# 13thISE_ver9.net
KiCad netlist of a schematic drawn in EAGLE
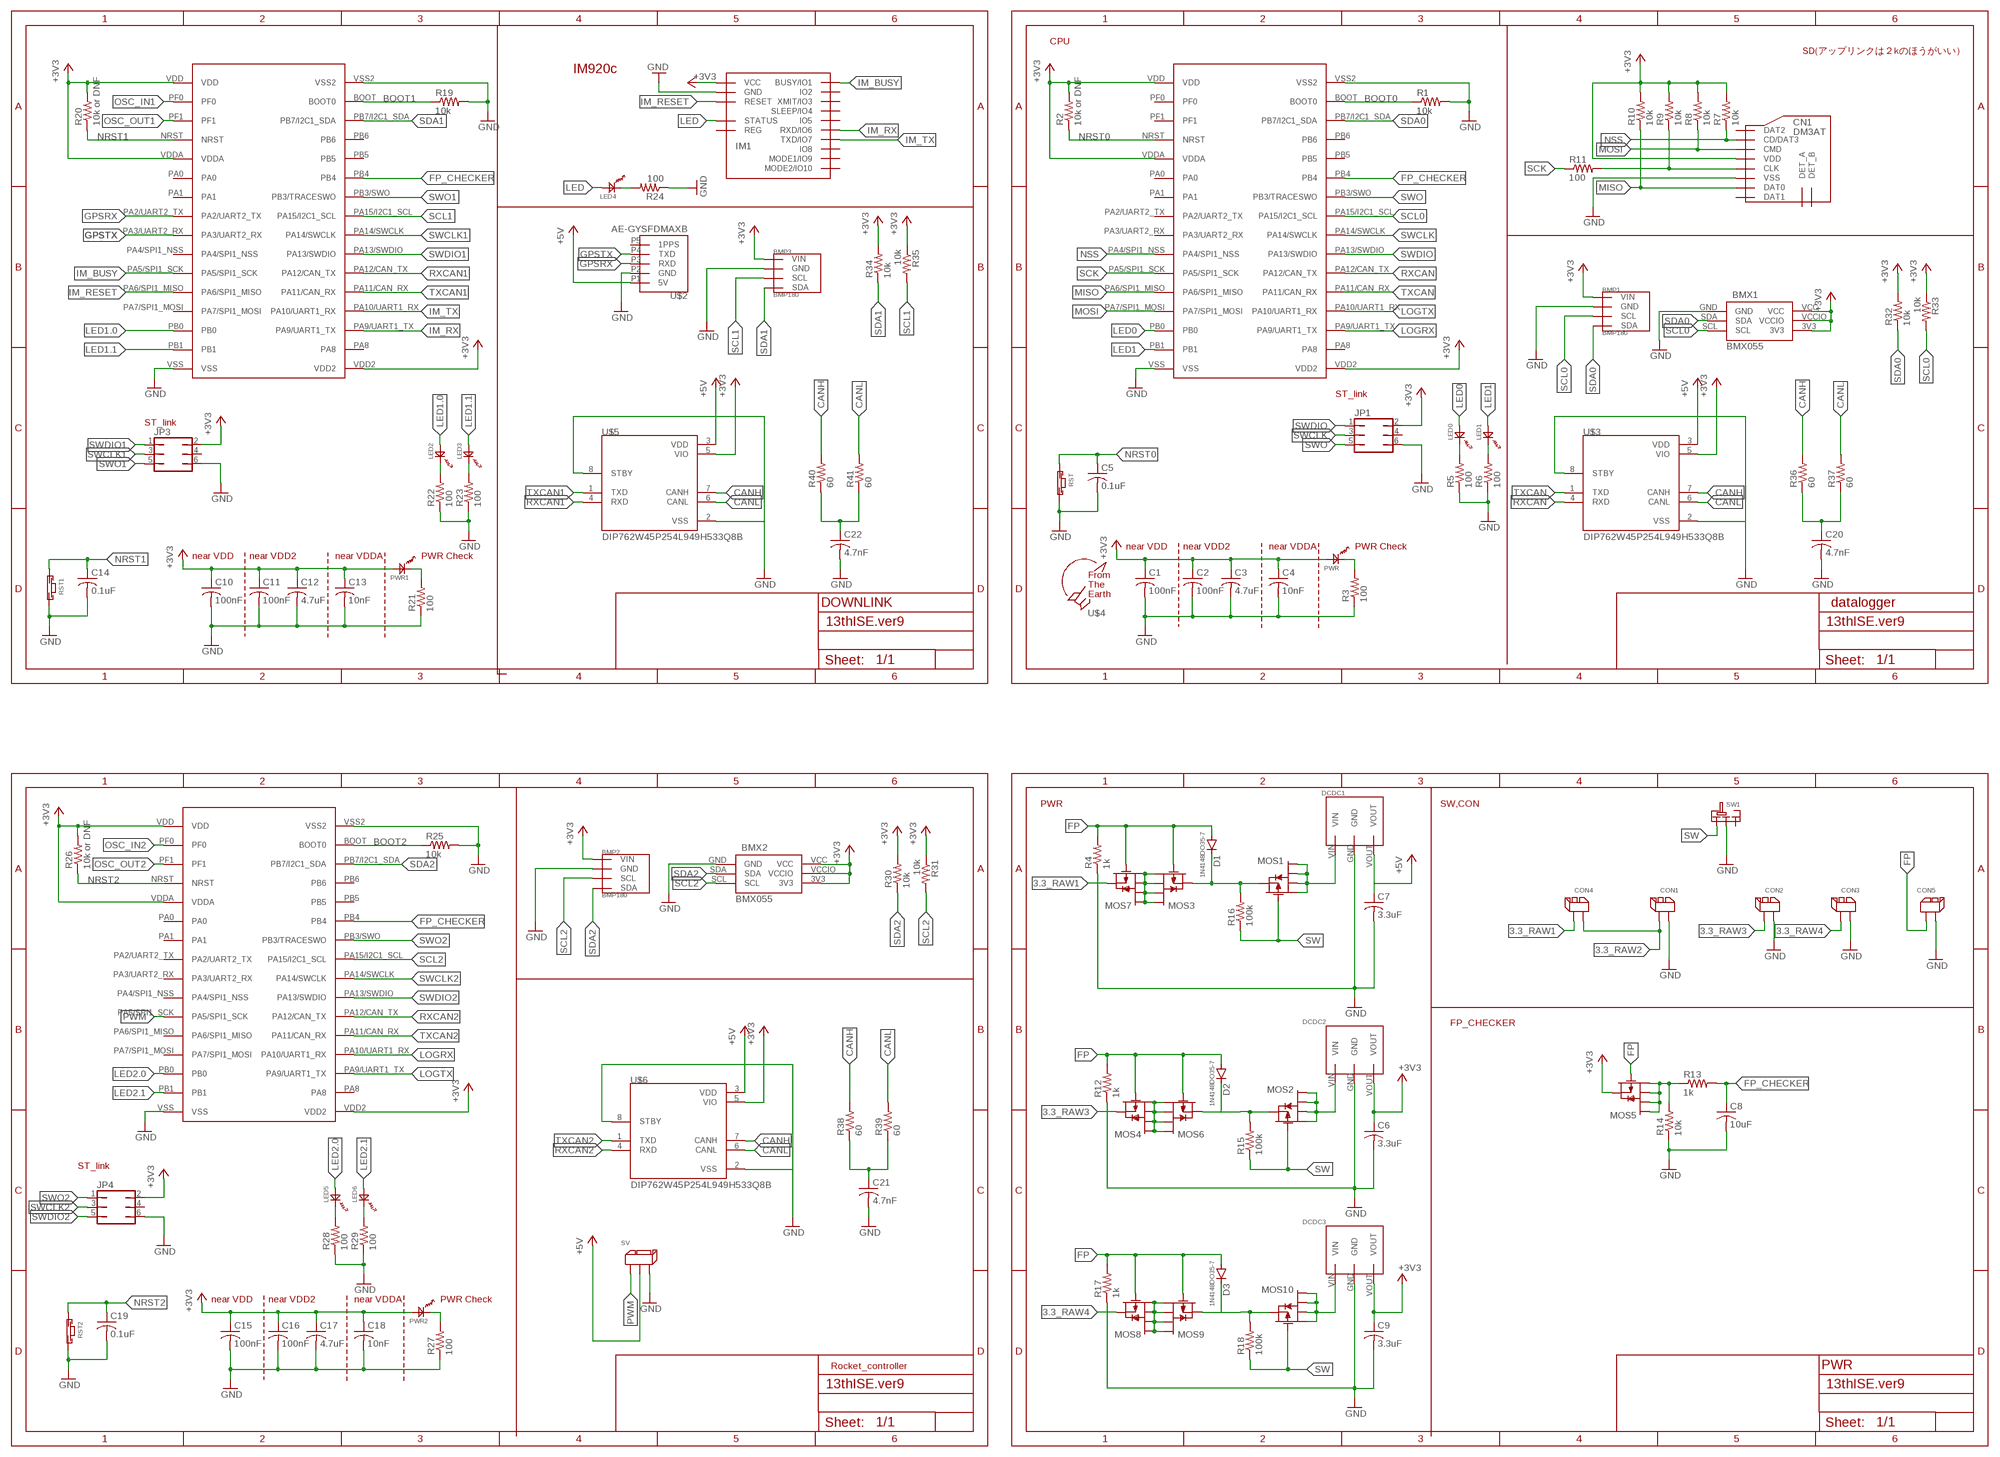
[diagram p0: schematic, sheet 1]

(export (version "E")
  (design (tool "Eeschema 10.0.6"))
  (components
    (comp (ref "BMP1")
      (value "BMP180")
      (footprint "eagle-import:GY-68")
      (libsource (lib "eagle-import") (part "BMP180"))
    )
    (comp (ref "BMP2")
      (value "BMP180")
      (footprint "eagle-import:GY-68")
      (libsource (lib "eagle-import") (part "BMP180"))
    )
    (comp (ref "BMP3")
      (value "BMP180")
      (footprint "eagle-import:GY-68")
      (libsource (lib "eagle-import") (part "BMP180"))
    )
    (comp (ref "BMX1")
      (value "BMX055")
      (footprint "eagle-import:BMX055")
      (libsource (lib "eagle-import") (part "BMX055"))
    )
    (comp (ref "BMX2")
      (value "BMX055")
      (footprint "eagle-import:BMX055")
      (libsource (lib "eagle-import") (part "BMX055"))
    )
    (comp (ref "C1")
      (value "100nF")
      (footprint "eagle-import:C1608")
      (libsource (lib "eagle-import") (part "C-USC1608"))
    )
    (comp (ref "C2")
      (value "100nF")
      (footprint "eagle-import:C1608")
      (libsource (lib "eagle-import") (part "C-USC1608"))
    )
    (comp (ref "C3")
      (value "4.7uF")
      (footprint "eagle-import:C1608")
      (libsource (lib "eagle-import") (part "C-USC1608"))
    )
    (comp (ref "C4")
      (value "10nF")
      (footprint "eagle-import:C1608")
      (libsource (lib "eagle-import") (part "C-USC1608"))
    )
    (comp (ref "C5")
      (value "0.1uF")
      (footprint "eagle-import:C1608")
      (libsource (lib "eagle-import") (part "C-USC1608"))
    )
    (comp (ref "C6")
      (value "3.3uF")
      (footprint "eagle-import:C0603")
      (libsource (lib "eagle-import") (part "C-USC0603"))
    )
    (comp (ref "C7")
      (value "3.3uF")
      (footprint "eagle-import:C0603")
      (libsource (lib "eagle-import") (part "C-USC0603"))
    )
    (comp (ref "C8")
      (value "10uF")
      (footprint "eagle-import:C0603")
      (libsource (lib "eagle-import") (part "C-USC0603"))
    )
    (comp (ref "C9")
      (value "3.3uF")
      (footprint "eagle-import:C0603")
      (libsource (lib "eagle-import") (part "C-USC0603"))
    )
    (comp (ref "C10")
      (value "100nF")
      (footprint "eagle-import:C1608")
      (libsource (lib "eagle-import") (part "C-USC1608"))
    )
    (comp (ref "C11")
      (value "100nF")
      (footprint "eagle-import:C1608")
      (libsource (lib "eagle-import") (part "C-USC1608"))
    )
    (comp (ref "C12")
      (value "4.7uF")
      (footprint "eagle-import:C1608")
      (libsource (lib "eagle-import") (part "C-USC1608"))
    )
    (comp (ref "C13")
      (value "10nF")
      (footprint "eagle-import:C1608")
      (libsource (lib "eagle-import") (part "C-USC1608"))
    )
    (comp (ref "C14")
      (value "0.1uF")
      (footprint "eagle-import:C1608")
      (libsource (lib "eagle-import") (part "C-USC1608"))
    )
    (comp (ref "C15")
      (value "100nF")
      (footprint "eagle-import:C1608")
      (libsource (lib "eagle-import") (part "C-USC1608"))
    )
    (comp (ref "C16")
      (value "100nF")
      (footprint "eagle-import:C1608")
      (libsource (lib "eagle-import") (part "C-USC1608"))
    )
    (comp (ref "C17")
      (value "4.7uF")
      (footprint "eagle-import:C1608")
      (libsource (lib "eagle-import") (part "C-USC1608"))
    )
    (comp (ref "C18")
      (value "10nF")
      (footprint "eagle-import:C1608")
      (libsource (lib "eagle-import") (part "C-USC1608"))
    )
    (comp (ref "C19")
      (value "0.1uF")
      (footprint "eagle-import:C1608")
      (libsource (lib "eagle-import") (part "C-USC1608"))
    )
    (comp (ref "C20")
      (value "4.7nF")
      (footprint "eagle-import:C0603")
      (libsource (lib "eagle-import") (part "C-USC0603"))
    )
    (comp (ref "C21")
      (value "4.7nF")
      (footprint "eagle-import:C0603")
      (libsource (lib "eagle-import") (part "C-USC0603"))
    )
    (comp (ref "C22")
      (value "4.7nF")
      (footprint "eagle-import:C0603")
      (libsource (lib "eagle-import") (part "C-USC0603"))
    )
    (comp (ref "CN1")
      (value "DM3AT")
      (footprint "eagle-import:DM3AT")
      (libsource (lib "eagle-import") (part "DM3AT"))
    )
    (comp (ref "CON1")
      (value "2PIN")
      (footprint "eagle-import:2PIN")
      (libsource (lib "eagle-import") (part "2PIN"))
    )
    (comp (ref "CON2")
      (value "2PIN")
      (footprint "eagle-import:2PIN")
      (libsource (lib "eagle-import") (part "2PIN"))
    )
    (comp (ref "CON3")
      (value "2PIN")
      (footprint "eagle-import:2PIN")
      (libsource (lib "eagle-import") (part "2PIN"))
    )
    (comp (ref "CON4")
      (value "2PIN")
      (footprint "eagle-import:2PIN")
      (libsource (lib "eagle-import") (part "2PIN"))
    )
    (comp (ref "CON5")
      (value "2PIN")
      (footprint "eagle-import:2PIN")
      (libsource (lib "eagle-import") (part "2PIN"))
    )
    (comp (ref "D1")
      (value "1N4148DO35-7")
      (footprint "eagle-import:DO35-7")
      (libsource (lib "eagle-import") (part "1N4148DO35-7"))
    )
    (comp (ref "D2")
      (value "1N4148DO35-7")
      (footprint "eagle-import:DO35-7")
      (libsource (lib "eagle-import") (part "1N4148DO35-7"))
    )
    (comp (ref "D3")
      (value "1N4148DO35-7")
      (footprint "eagle-import:DO35-7")
      (libsource (lib "eagle-import") (part "1N4148DO35-7"))
    )
    (comp (ref "DCDC1")
      (value "5V1A_M78AR05-1")
      (footprint "eagle-import:5V1A_M78AR05-1")
      (libsource (lib "eagle-import") (part "5V1A_M78AR05-1"))
    )
    (comp (ref "DCDC2")
      (value "3.3V1A_M78AR033-1")
      (footprint "eagle-import:3.3V1A_M78AR033-1")
      (libsource (lib "eagle-import") (part "3.3V1A_M78AR033-1"))
    )
    (comp (ref "DCDC3")
      (value "3.3V1A_M78AR033-1")
      (footprint "eagle-import:3.3V1A_M78AR033-1")
      (libsource (lib "eagle-import") (part "3.3V1A_M78AR033-1"))
    )
    (comp (ref "IM1")
      (value "IM920_IM920C")
      (footprint "eagle-import:IM920_IM920C")
      (libsource (lib "eagle-import") (part "IM920_IM920C"))
    )
    (comp (ref "JP1")
      (value "JP3Q")
      (footprint "eagle-import:JP3Q")
      (libsource (lib "eagle-import") (part "JP3Q"))
    )
    (comp (ref "JP3")
      (value "JP3Q")
      (footprint "eagle-import:JP3Q")
      (libsource (lib "eagle-import") (part "JP3Q"))
    )
    (comp (ref "JP4")
      (value "JP3Q")
      (footprint "eagle-import:JP3Q")
      (libsource (lib "eagle-import") (part "JP3Q"))
    )
    (comp (ref "LED0")
      (value "OSXX1608C1A")
      (footprint "eagle-import:OSXX1608C1A")
      (libsource (lib "eagle-import") (part "OSXX1608C1A"))
    )
    (comp (ref "LED1")
      (value "OSXX1608C1A")
      (footprint "eagle-import:OSXX1608C1A")
      (libsource (lib "eagle-import") (part "OSXX1608C1A"))
    )
    (comp (ref "LED2")
      (value "OSXX1608C1A")
      (footprint "eagle-import:OSXX1608C1A")
      (libsource (lib "eagle-import") (part "OSXX1608C1A"))
    )
    (comp (ref "LED3")
      (value "OSXX1608C1A")
      (footprint "eagle-import:OSXX1608C1A")
      (libsource (lib "eagle-import") (part "OSXX1608C1A"))
    )
    (comp (ref "LED4")
      (value "OSXX1608C1A")
      (footprint "eagle-import:OSXX1608C1A")
      (libsource (lib "eagle-import") (part "OSXX1608C1A"))
    )
    (comp (ref "LED5")
      (value "OSXX1608C1A")
      (footprint "eagle-import:OSXX1608C1A")
      (libsource (lib "eagle-import") (part "OSXX1608C1A"))
    )
    (comp (ref "LED6")
      (value "OSXX1608C1A")
      (footprint "eagle-import:OSXX1608C1A")
      (libsource (lib "eagle-import") (part "OSXX1608C1A"))
    )
    (comp (ref "MOS1")
      (value "PCH_SSM6J808R")
      (footprint "eagle-import:SSM6J808R")
      (libsource (lib "eagle-import") (part "PCH_SSM6J808R"))
    )
    (comp (ref "MOS2")
      (value "PCH_SSM6J808R")
      (footprint "eagle-import:SSM6J808R")
      (libsource (lib "eagle-import") (part "PCH_SSM6J808R"))
    )
    (comp (ref "MOS3")
      (value "PCH_SSM6J808R")
      (footprint "eagle-import:SSM6J808R")
      (libsource (lib "eagle-import") (part "PCH_SSM6J808R"))
    )
    (comp (ref "MOS4")
      (value "PCH_SSM6J808R")
      (footprint "eagle-import:SSM6J808R")
      (libsource (lib "eagle-import") (part "PCH_SSM6J808R"))
    )
    (comp (ref "MOS5")
      (value "PCH_SSM6J808R")
      (footprint "eagle-import:SSM6J808R")
      (libsource (lib "eagle-import") (part "PCH_SSM6J808R"))
    )
    (comp (ref "MOS6")
      (value "PCH_SSM6J808R")
      (footprint "eagle-import:SSM6J808R")
      (libsource (lib "eagle-import") (part "PCH_SSM6J808R"))
    )
    (comp (ref "MOS7")
      (value "PCH_SSM6J808R")
      (footprint "eagle-import:SSM6J808R")
      (libsource (lib "eagle-import") (part "PCH_SSM6J808R"))
    )
    (comp (ref "MOS8")
      (value "PCH_SSM6J808R")
      (footprint "eagle-import:SSM6J808R")
      (libsource (lib "eagle-import") (part "PCH_SSM6J808R"))
    )
    (comp (ref "MOS9")
      (value "PCH_SSM6J808R")
      (footprint "eagle-import:SSM6J808R")
      (libsource (lib "eagle-import") (part "PCH_SSM6J808R"))
    )
    (comp (ref "MOS10")
      (value "PCH_SSM6J808R")
      (footprint "eagle-import:SSM6J808R")
      (libsource (lib "eagle-import") (part "PCH_SSM6J808R"))
    )
    (comp (ref "PWR")
      (value "OSXX1608C1A")
      (footprint "eagle-import:OSXX1608C1A")
      (libsource (lib "eagle-import") (part "OSXX1608C1A"))
    )
    (comp (ref "PWR1")
      (value "OSXX1608C1A")
      (footprint "eagle-import:OSXX1608C1A")
      (libsource (lib "eagle-import") (part "OSXX1608C1A"))
    )
    (comp (ref "PWR2")
      (value "OSXX1608C1A")
      (footprint "eagle-import:OSXX1608C1A")
      (libsource (lib "eagle-import") (part "OSXX1608C1A"))
    )
    (comp (ref "R1")
      (value "10k")
      (footprint "eagle-import:R0603")
      (libsource (lib "eagle-import") (part "R-US_R0603"))
    )
    (comp (ref "R2")
      (value "10k or DNF")
      (footprint "eagle-import:R0603")
      (libsource (lib "eagle-import") (part "R-US_R0603"))
    )
    (comp (ref "R3")
      (value "100")
      (footprint "eagle-import:R0603")
      (libsource (lib "eagle-import") (part "R-US_R0603"))
    )
    (comp (ref "R4")
      (value "1k")
      (footprint "eagle-import:R0603")
      (libsource (lib "eagle-import") (part "R-US_R0603"))
    )
    (comp (ref "R5")
      (value "100")
      (footprint "eagle-import:R0603")
      (libsource (lib "eagle-import") (part "R-US_R0603"))
    )
    (comp (ref "R6")
      (value "100")
      (footprint "eagle-import:R0603")
      (libsource (lib "eagle-import") (part "R-US_R0603"))
    )
    (comp (ref "R7")
      (value "10k")
      (footprint "eagle-import:R0603")
      (libsource (lib "eagle-import") (part "R-US_R0603"))
    )
    (comp (ref "R8")
      (value "10k")
      (footprint "eagle-import:R0603")
      (libsource (lib "eagle-import") (part "R-US_R0603"))
    )
    (comp (ref "R9")
      (value "10k")
      (footprint "eagle-import:R0603")
      (libsource (lib "eagle-import") (part "R-US_R0603"))
    )
    (comp (ref "R10")
      (value "10k")
      (footprint "eagle-import:R0603")
      (libsource (lib "eagle-import") (part "R-US_R0603"))
    )
    (comp (ref "R11")
      (value "100")
      (footprint "eagle-import:R0603")
      (libsource (lib "eagle-import") (part "R-US_R0603"))
    )
    (comp (ref "R12")
      (value "1k")
      (footprint "eagle-import:R0603")
      (libsource (lib "eagle-import") (part "R-US_R0603"))
    )
    (comp (ref "R13")
      (value "1k")
      (footprint "eagle-import:R0603")
      (libsource (lib "eagle-import") (part "R-US_R0603"))
    )
    (comp (ref "R14")
      (value "10k")
      (footprint "eagle-import:R0603")
      (libsource (lib "eagle-import") (part "R-US_R0603"))
    )
    (comp (ref "R15")
      (value "100k")
      (footprint "eagle-import:R0603")
      (libsource (lib "eagle-import") (part "R-US_R0603"))
    )
    (comp (ref "R16")
      (value "100k")
      (footprint "eagle-import:R0603")
      (libsource (lib "eagle-import") (part "R-US_R0603"))
    )
    (comp (ref "R17")
      (value "1k")
      (footprint "eagle-import:R0603")
      (libsource (lib "eagle-import") (part "R-US_R0603"))
    )
    (comp (ref "R18")
      (value "100k")
      (footprint "eagle-import:R0603")
      (libsource (lib "eagle-import") (part "R-US_R0603"))
    )
    (comp (ref "R19")
      (value "10k")
      (footprint "eagle-import:R0603")
      (libsource (lib "eagle-import") (part "R-US_R0603"))
    )
    (comp (ref "R20")
      (value "10k or DNF")
      (footprint "eagle-import:R0603")
      (libsource (lib "eagle-import") (part "R-US_R0603"))
    )
    (comp (ref "R21")
      (value "100")
      (footprint "eagle-import:R0603")
      (libsource (lib "eagle-import") (part "R-US_R0603"))
    )
    (comp (ref "R22")
      (value "100")
      (footprint "eagle-import:R0603")
      (libsource (lib "eagle-import") (part "R-US_R0603"))
    )
    (comp (ref "R23")
      (value "100")
      (footprint "eagle-import:R0603")
      (libsource (lib "eagle-import") (part "R-US_R0603"))
    )
    (comp (ref "R24")
      (value "100")
      (footprint "eagle-import:R0603")
      (libsource (lib "eagle-import") (part "R-US_R0603"))
    )
    (comp (ref "R25")
      (value "10k")
      (footprint "eagle-import:R0603")
      (libsource (lib "eagle-import") (part "R-US_R0603"))
    )
    (comp (ref "R26")
      (value "10k or DNF")
      (footprint "eagle-import:R0603")
      (libsource (lib "eagle-import") (part "R-US_R0603"))
    )
    (comp (ref "R27")
      (value "100")
      (footprint "eagle-import:R0603")
      (libsource (lib "eagle-import") (part "R-US_R0603"))
    )
    (comp (ref "R28")
      (value "100")
      (footprint "eagle-import:R0603")
      (libsource (lib "eagle-import") (part "R-US_R0603"))
    )
    (comp (ref "R29")
      (value "100")
      (footprint "eagle-import:R0603")
      (libsource (lib "eagle-import") (part "R-US_R0603"))
    )
    (comp (ref "R30")
      (value "10k")
      (footprint "eagle-import:R0603")
      (libsource (lib "eagle-import") (part "R-US_R0603"))
    )
    (comp (ref "R31")
      (value "10k")
      (footprint "eagle-import:R0603")
      (libsource (lib "eagle-import") (part "R-US_R0603"))
    )
    (comp (ref "R32")
      (value "10k")
      (footprint "eagle-import:R0603")
      (libsource (lib "eagle-import") (part "R-US_R0603"))
    )
    (comp (ref "R33")
      (value "10k")
      (footprint "eagle-import:R0603")
      (libsource (lib "eagle-import") (part "R-US_R0603"))
    )
    (comp (ref "R34")
      (value "10k")
      (footprint "eagle-import:R0603")
      (libsource (lib "eagle-import") (part "R-US_R0603"))
    )
    (comp (ref "R35")
      (value "10k")
      (footprint "eagle-import:R0603")
      (libsource (lib "eagle-import") (part "R-US_R0603"))
    )
    (comp (ref "R36")
      (value "60")
      (footprint "eagle-import:R0603")
      (libsource (lib "eagle-import") (part "R-US_R0603"))
    )
    (comp (ref "R37")
      (value "60")
      (footprint "eagle-import:R0603")
      (libsource (lib "eagle-import") (part "R-US_R0603"))
    )
    (comp (ref "R38")
      (value "60")
      (footprint "eagle-import:R0603")
      (libsource (lib "eagle-import") (part "R-US_R0603"))
    )
    (comp (ref "R39")
      (value "60")
      (footprint "eagle-import:R0603")
      (libsource (lib "eagle-import") (part "R-US_R0603"))
    )
    (comp (ref "R40")
      (value "60")
      (footprint "eagle-import:R0603")
      (libsource (lib "eagle-import") (part "R-US_R0603"))
    )
    (comp (ref "R41")
      (value "60")
      (footprint "eagle-import:R0603")
      (libsource (lib "eagle-import") (part "R-US_R0603"))
    )
    (comp (ref "RST")
      (value "TVAF06-A020B-R")
      (footprint "eagle-import:TVAF06-A020B-R")
      (libsource (lib "eagle-import") (part "TVAF06-A020B-R"))
    )
    (comp (ref "RST1")
      (value "TVAF06-A020B-R")
      (footprint "eagle-import:TVAF06-A020B-R")
      (libsource (lib "eagle-import") (part "TVAF06-A020B-R"))
    )
    (comp (ref "RST2")
      (value "TVAF06-A020B-R")
      (footprint "eagle-import:TVAF06-A020B-R")
      (libsource (lib "eagle-import") (part "TVAF06-A020B-R"))
    )
    (comp (ref "STM0")
      (value "STM32F303K8")
      (footprint "eagle-import:STM32F303K8")
      (libsource (lib "eagle-import") (part "STM32F303K8"))
    )
    (comp (ref "STM1")
      (value "STM32F303K8")
      (footprint "eagle-import:STM32F303K8")
      (libsource (lib "eagle-import") (part "STM32F303K8"))
    )
    (comp (ref "SV")
      (value "3PIN")
      (footprint "eagle-import:3PIN")
      (libsource (lib "eagle-import") (part "3PIN"))
    )
    (comp (ref "SW1")
      (value "SRIDE_SWITCH")
      (footprint "eagle-import:SRIDE_SWITCH")
      (libsource (lib "eagle-import") (part "SRIDE_SWITCH"))
    )
    (comp (ref "U$1")
      (value "STM32F303K8")
      (footprint "eagle-import:STM32F303K8")
      (libsource (lib "eagle-import") (part "STM32F303K8"))
    )
    (comp (ref "U$2")
      (value "AE-GYSFDMAXB")
      (footprint "eagle-import:AE-GYSFDMAXB")
      (libsource (lib "eagle-import") (part "AE-GYSFDMAXB"))
    )
    (comp (ref "U$3")
      (value "DIP762W45P254L949H533Q8B")
      (footprint "eagle-import:DIP762W45P254L949H533Q8B")
      (libsource (lib "eagle-import") (part "DIP762W45P254L949H533Q8B"))
    )
    (comp (ref "U$4")
      (value "F.T.E.LOGO")
      (footprint "eagle-import:LOGO")
      (libsource (lib "eagle-import") (part "F.T.E.LOGO"))
    )
    (comp (ref "U$5")
      (value "DIP762W45P254L949H533Q8B")
      (footprint "eagle-import:DIP762W45P254L949H533Q8B")
      (libsource (lib "eagle-import") (part "DIP762W45P254L949H533Q8B"))
    )
    (comp (ref "U$6")
      (value "DIP762W45P254L949H533Q8B")
      (footprint "eagle-import:DIP762W45P254L949H533Q8B")
      (libsource (lib "eagle-import") (part "DIP762W45P254L949H533Q8B"))
    )
  )
  (nets
    (net (code "1") (name "+3V3") (class "Default")
      (node (ref "BMP1") (pin "P1") (pinfunction "VIN_P1") (pintype "bidirectional"))
      (node (ref "BMP2") (pin "P1") (pinfunction "VIN_P1") (pintype "bidirectional"))
      (node (ref "BMP3") (pin "P1") (pinfunction "VIN_P1") (pintype "bidirectional"))
      (node (ref "BMX1") (pin "3V3") (pinfunction "3V3_3V3") (pintype "power_in"))
      (node (ref "BMX1") (pin "VCC") (pinfunction "VCC_VCC") (pintype "power_in"))
      (node (ref "BMX1") (pin "VCCIO") (pinfunction "VCCIO_VCCIO") (pintype "power_in"))
      (node (ref "BMX2") (pin "3V3") (pinfunction "3V3_3V3") (pintype "power_in"))
      (node (ref "BMX2") (pin "VCC") (pinfunction "VCC_VCC") (pintype "power_in"))
      (node (ref "BMX2") (pin "VCCIO") (pinfunction "VCCIO_VCCIO") (pintype "power_in"))
      (node (ref "C1") (pin "1") (pinfunction "1_1") (pintype "passive"))
      (node (ref "C10") (pin "1") (pinfunction "1_1") (pintype "passive"))
      (node (ref "C11") (pin "1") (pinfunction "1_1") (pintype "passive"))
      (node (ref "C12") (pin "1") (pinfunction "1_1") (pintype "passive"))
      (node (ref "C13") (pin "1") (pinfunction "1_1") (pintype "passive"))
      (node (ref "C15") (pin "1") (pinfunction "1_1") (pintype "passive"))
      (node (ref "C16") (pin "1") (pinfunction "1_1") (pintype "passive"))
      (node (ref "C17") (pin "1") (pinfunction "1_1") (pintype "passive"))
      (node (ref "C18") (pin "1") (pinfunction "1_1") (pintype "passive"))
      (node (ref "C2") (pin "1") (pinfunction "1_1") (pintype "passive"))
      (node (ref "C3") (pin "1") (pinfunction "1_1") (pintype "passive"))
      (node (ref "C4") (pin "1") (pinfunction "1_1") (pintype "passive"))
      (node (ref "C6") (pin "1") (pinfunction "1_1") (pintype "passive"))
      (node (ref "C9") (pin "1") (pinfunction "1_1") (pintype "passive"))
      (node (ref "CN1") (pin "VDD") (pinfunction "VDD_VDD") (pintype "bidirectional"))
      (node (ref "DCDC2") (pin "VOUT") (pinfunction "VOUT_VOUT") (pintype "bidirectional"))
      (node (ref "DCDC3") (pin "VOUT") (pinfunction "VOUT_VOUT") (pintype "bidirectional"))
      (node (ref "IM1") (pin "$P17") (pinfunction "VCC_$P17") (pintype "bidirectional"))
      (node (ref "JP1") (pin "2") (pinfunction "2_2") (pintype "passive"))
      (node (ref "JP3") (pin "2") (pinfunction "2_2") (pintype "passive"))
      (node (ref "JP4") (pin "2") (pinfunction "2_2") (pintype "passive"))
      (node (ref "MOS5") (pin "4") (pinfunction "4_4") (pintype "bidirectional"))
      (node (ref "PWR") (pin "AN") (pinfunction "AN_AN") (pintype "bidirectional"))
      (node (ref "PWR1") (pin "AN") (pinfunction "AN_AN") (pintype "bidirectional"))
      (node (ref "PWR2") (pin "AN") (pinfunction "AN_AN") (pintype "bidirectional"))
      (node (ref "R10") (pin "2") (pinfunction "2_2") (pintype "passive"))
      (node (ref "R2") (pin "2") (pinfunction "2_2") (pintype "passive"))
      (node (ref "R20") (pin "2") (pinfunction "2_2") (pintype "passive"))
      (node (ref "R26") (pin "2") (pinfunction "2_2") (pintype "passive"))
      (node (ref "R30") (pin "2") (pinfunction "2_2") (pintype "passive"))
      (node (ref "R31") (pin "1") (pinfunction "1_1") (pintype "passive"))
      (node (ref "R32") (pin "2") (pinfunction "2_2") (pintype "passive"))
      (node (ref "R33") (pin "1") (pinfunction "1_1") (pintype "passive"))
      (node (ref "R34") (pin "2") (pinfunction "2_2") (pintype "passive"))
      (node (ref "R35") (pin "1") (pinfunction "1_1") (pintype "passive"))
      (node (ref "R7") (pin "2") (pinfunction "2_2") (pintype "passive"))
      (node (ref "R8") (pin "2") (pinfunction "2_2") (pintype "passive"))
      (node (ref "R9") (pin "2") (pinfunction "2_2") (pintype "passive"))
      (node (ref "STM0") (pin "VDD") (pinfunction "VDD_VDD") (pintype "power_in"))
      (node (ref "STM0") (pin "VDD2") (pinfunction "VDD2_VDD2") (pintype "power_in"))
      (node (ref "STM0") (pin "VDDA") (pinfunction "VDDA_VDDA") (pintype "power_in"))
      (node (ref "STM1") (pin "VDD") (pinfunction "VDD_VDD") (pintype "power_in"))
      (node (ref "STM1") (pin "VDD2") (pinfunction "VDD2_VDD2") (pintype "power_in"))
      (node (ref "STM1") (pin "VDDA") (pinfunction "VDDA_VDDA") (pintype "power_in"))
      (node (ref "U$1") (pin "VDD") (pinfunction "VDD_VDD") (pintype "power_in"))
      (node (ref "U$1") (pin "VDD2") (pinfunction "VDD2_VDD2") (pintype "power_in"))
      (node (ref "U$1") (pin "VDDA") (pinfunction "VDDA_VDDA") (pintype "power_in"))
      (node (ref "U$3") (pin "5") (pinfunction "VIO_5") (pintype "power_in"))
      (node (ref "U$5") (pin "5") (pinfunction "VIO_5") (pintype "power_in"))
      (node (ref "U$6") (pin "5") (pinfunction "VIO_5") (pintype "power_in"))
    )
    (net (code "2") (name "+5V") (class "Default")
      (node (ref "C7") (pin "1") (pinfunction "1_1") (pintype "passive"))
      (node (ref "DCDC1") (pin "VOUT") (pinfunction "VOUT_VOUT") (pintype "bidirectional"))
      (node (ref "SV") (pin "P$2") (pinfunction "P$2_P$2") (pintype "bidirectional"))
      (node (ref "U$2") (pin "P1") (pinfunction "5V_P1") (pintype "bidirectional"))
      (node (ref "U$3") (pin "3") (pinfunction "VDD_3") (pintype "power_in"))
      (node (ref "U$5") (pin "3") (pinfunction "VDD_3") (pintype "power_in"))
      (node (ref "U$6") (pin "3") (pinfunction "VDD_3") (pintype "power_in"))
    )
    (net (code "3") (name "/BOOT0") (class "Default")
      (node (ref "R1") (pin "1") (pinfunction "1_1") (pintype "passive"))
      (node (ref "STM0") (pin "BOOT") (pinfunction "BOOT0_BOOT") (pintype "bidirectional"))
    )
    (net (code "4") (name "/BOOT1") (class "Default")
      (node (ref "R19") (pin "1") (pinfunction "1_1") (pintype "passive"))
      (node (ref "STM1") (pin "BOOT") (pinfunction "BOOT0_BOOT") (pintype "bidirectional"))
    )
    (net (code "5") (name "/BOOT2") (class "Default")
      (node (ref "R25") (pin "1") (pinfunction "1_1") (pintype "passive"))
      (node (ref "U$1") (pin "BOOT") (pinfunction "BOOT0_BOOT") (pintype "bidirectional"))
    )
    (net (code "6") (name "3.3_RAW1") (class "Default")
      (node (ref "CON4") (pin "P$2") (pinfunction "P$2_P$2") (pintype "bidirectional"))
      (node (ref "MOS7") (pin "4") (pinfunction "4_4") (pintype "bidirectional"))
    )
    (net (code "7") (name "3.3_RAW2") (class "Default")
      (node (ref "CON1") (pin "P$2") (pinfunction "P$2_P$2") (pintype "bidirectional"))
      (node (ref "CON4") (pin "P$1") (pinfunction "P$1_P$1") (pintype "bidirectional"))
    )
    (net (code "8") (name "3.3_RAW3") (class "Default")
      (node (ref "CON2") (pin "P$2") (pinfunction "P$2_P$2") (pintype "bidirectional"))
      (node (ref "MOS4") (pin "4") (pinfunction "4_4") (pintype "bidirectional"))
    )
    (net (code "9") (name "3.3_RAW4") (class "Default")
      (node (ref "CON3") (pin "P$2") (pinfunction "P$2_P$2") (pintype "bidirectional"))
      (node (ref "MOS8") (pin "4") (pinfunction "4_4") (pintype "bidirectional"))
    )
    (net (code "10") (name "CANH") (class "Default")
      (node (ref "R36") (pin "2") (pinfunction "2_2") (pintype "passive"))
      (node (ref "R38") (pin "2") (pinfunction "2_2") (pintype "passive"))
      (node (ref "R40") (pin "2") (pinfunction "2_2") (pintype "passive"))
      (node (ref "U$3") (pin "7") (pinfunction "CANH_7") (pintype "bidirectional"))
      (node (ref "U$5") (pin "7") (pinfunction "CANH_7") (pintype "bidirectional"))
      (node (ref "U$6") (pin "7") (pinfunction "CANH_7") (pintype "bidirectional"))
    )
    (net (code "11") (name "CANL") (class "Default")
      (node (ref "R37") (pin "2") (pinfunction "2_2") (pintype "passive"))
      (node (ref "R39") (pin "2") (pinfunction "2_2") (pintype "passive"))
      (node (ref "R41") (pin "2") (pinfunction "2_2") (pintype "passive"))
      (node (ref "U$3") (pin "6") (pinfunction "CANL_6") (pintype "bidirectional"))
      (node (ref "U$5") (pin "6") (pinfunction "CANL_6") (pintype "bidirectional"))
      (node (ref "U$6") (pin "6") (pinfunction "CANL_6") (pintype "bidirectional"))
    )
    (net (code "12") (name "FP") (class "Default")
      (node (ref "CON5") (pin "P$1") (pinfunction "P$1_P$1") (pintype "bidirectional"))
      (node (ref "D1") (pin "A") (pinfunction "A_A") (pintype "passive"))
      (node (ref "D2") (pin "A") (pinfunction "A_A") (pintype "passive"))
      (node (ref "D3") (pin "A") (pinfunction "A_A") (pintype "passive"))
      (node (ref "MOS3") (pin "3") (pinfunction "3_3") (pintype "bidirectional"))
      (node (ref "MOS4") (pin "3") (pinfunction "3_3") (pintype "bidirectional"))
      (node (ref "MOS5") (pin "3") (pinfunction "3_3") (pintype "bidirectional"))
      (node (ref "MOS6") (pin "3") (pinfunction "3_3") (pintype "bidirectional"))
      (node (ref "MOS7") (pin "3") (pinfunction "3_3") (pintype "bidirectional"))
      (node (ref "MOS8") (pin "3") (pinfunction "3_3") (pintype "bidirectional"))
      (node (ref "MOS9") (pin "3") (pinfunction "3_3") (pintype "bidirectional"))
      (node (ref "R12") (pin "2") (pinfunction "2_2") (pintype "passive"))
      (node (ref "R17") (pin "2") (pinfunction "2_2") (pintype "passive"))
      (node (ref "R4") (pin "2") (pinfunction "2_2") (pintype "passive"))
    )
    (net (code "13") (name "FP_CHECKER") (class "Default")
      (node (ref "C8") (pin "1") (pinfunction "1_1") (pintype "passive"))
      (node (ref "R13") (pin "2") (pinfunction "2_2") (pintype "passive"))
      (node (ref "STM0") (pin "PB4") (pinfunction "PB4_PB4") (pintype "bidirectional"))
      (node (ref "STM1") (pin "PB4") (pinfunction "PB4_PB4") (pintype "bidirectional"))
      (node (ref "U$1") (pin "PB4") (pinfunction "PB4_PB4") (pintype "bidirectional"))
    )
    (net (code "14") (name "GND") (class "Default")
      (node (ref "BMP1") (pin "P2") (pinfunction "GND_P2") (pintype "bidirectional"))
      (node (ref "BMP2") (pin "P2") (pinfunction "GND_P2") (pintype "bidirectional"))
      (node (ref "BMP3") (pin "P2") (pinfunction "GND_P2") (pintype "bidirectional"))
      (node (ref "BMX1") (pin "GND") (pinfunction "GND_GND") (pintype "power_in"))
      (node (ref "BMX2") (pin "GND") (pinfunction "GND_GND") (pintype "power_in"))
      (node (ref "C1") (pin "2") (pinfunction "2_2") (pintype "passive"))
      (node (ref "C10") (pin "2") (pinfunction "2_2") (pintype "passive"))
      (node (ref "C11") (pin "2") (pinfunction "2_2") (pintype "passive"))
      (node (ref "C12") (pin "2") (pinfunction "2_2") (pintype "passive"))
      (node (ref "C13") (pin "2") (pinfunction "2_2") (pintype "passive"))
      (node (ref "C14") (pin "2") (pinfunction "2_2") (pintype "passive"))
      (node (ref "C15") (pin "2") (pinfunction "2_2") (pintype "passive"))
      (node (ref "C16") (pin "2") (pinfunction "2_2") (pintype "passive"))
      (node (ref "C17") (pin "2") (pinfunction "2_2") (pintype "passive"))
      (node (ref "C18") (pin "2") (pinfunction "2_2") (pintype "passive"))
      (node (ref "C19") (pin "2") (pinfunction "2_2") (pintype "passive"))
      (node (ref "C2") (pin "2") (pinfunction "2_2") (pintype "passive"))
      (node (ref "C20") (pin "2") (pinfunction "2_2") (pintype "passive"))
      (node (ref "C21") (pin "2") (pinfunction "2_2") (pintype "passive"))
      (node (ref "C22") (pin "2") (pinfunction "2_2") (pintype "passive"))
      (node (ref "C3") (pin "2") (pinfunction "2_2") (pintype "passive"))
      (node (ref "C4") (pin "2") (pinfunction "2_2") (pintype "passive"))
      (node (ref "C5") (pin "2") (pinfunction "2_2") (pintype "passive"))
      (node (ref "C6") (pin "2") (pinfunction "2_2") (pintype "passive"))
      (node (ref "C7") (pin "2") (pinfunction "2_2") (pintype "passive"))
      (node (ref "C8") (pin "2") (pinfunction "2_2") (pintype "passive"))
      (node (ref "C9") (pin "2") (pinfunction "2_2") (pintype "passive"))
      (node (ref "CN1") (pin "VSS") (pinfunction "VSS_VSS") (pintype "bidirectional"))
      (node (ref "CON1") (pin "P$1") (pinfunction "P$1_P$1") (pintype "bidirectional"))
      (node (ref "CON2") (pin "P$1") (pinfunction "P$1_P$1") (pintype "bidirectional"))
      (node (ref "CON3") (pin "P$1") (pinfunction "P$1_P$1") (pintype "bidirectional"))
      (node (ref "CON5") (pin "P$2") (pinfunction "P$2_P$2") (pintype "bidirectional"))
      (node (ref "DCDC1") (pin "GND") (pinfunction "GND_GND") (pintype "bidirectional"))
      (node (ref "DCDC2") (pin "GND") (pinfunction "GND_GND") (pintype "bidirectional"))
      (node (ref "DCDC3") (pin "GND") (pinfunction "GND_GND") (pintype "bidirectional"))
      (node (ref "IM1") (pin "$P18") (pinfunction "GND_$P18") (pintype "bidirectional"))
      (node (ref "JP1") (pin "6") (pinfunction "6_6") (pintype "passive"))
      (node (ref "JP3") (pin "6") (pinfunction "6_6") (pintype "passive"))
      (node (ref "JP4") (pin "6") (pinfunction "6_6") (pintype "passive"))
      (node (ref "R1") (pin "2") (pinfunction "2_2") (pintype "passive"))
      (node (ref "R12") (pin "1") (pinfunction "1_1") (pintype "passive"))
      (node (ref "R14") (pin "1") (pinfunction "1_1") (pintype "passive"))
      (node (ref "R17") (pin "1") (pinfunction "1_1") (pintype "passive"))
      (node (ref "R19") (pin "2") (pinfunction "2_2") (pintype "passive"))
      (node (ref "R21") (pin "1") (pinfunction "1_1") (pintype "passive"))
      (node (ref "R22") (pin "1") (pinfunction "1_1") (pintype "passive"))
      (node (ref "R23") (pin "1") (pinfunction "1_1") (pintype "passive"))
      (node (ref "R24") (pin "1") (pinfunction "1_1") (pintype "passive"))
      (node (ref "R25") (pin "2") (pinfunction "2_2") (pintype "passive"))
      (node (ref "R27") (pin "1") (pinfunction "1_1") (pintype "passive"))
      (node (ref "R28") (pin "1") (pinfunction "1_1") (pintype "passive"))
      (node (ref "R29") (pin "1") (pinfunction "1_1") (pintype "passive"))
      (node (ref "R3") (pin "1") (pinfunction "1_1") (pintype "passive"))
      (node (ref "R4") (pin "1") (pinfunction "1_1") (pintype "passive"))
      (node (ref "R5") (pin "1") (pinfunction "1_1") (pintype "passive"))
      (node (ref "R6") (pin "1") (pinfunction "1_1") (pintype "passive"))
      (node (ref "RST") (pin "P$2") (pinfunction "P$2_P$2") (pintype "bidirectional"))
      (node (ref "RST1") (pin "P$2") (pinfunction "P$2_P$2") (pintype "bidirectional"))
      (node (ref "RST2") (pin "P$2") (pinfunction "P$2_P$2") (pintype "bidirectional"))
      (node (ref "STM0") (pin "VSS") (pinfunction "VSS_VSS") (pintype "power_in"))
      (node (ref "STM0") (pin "VSS2") (pinfunction "VSS2_VSS2") (pintype "power_in"))
      (node (ref "STM1") (pin "VSS") (pinfunction "VSS_VSS") (pintype "power_in"))
      (node (ref "STM1") (pin "VSS2") (pinfunction "VSS2_VSS2") (pintype "power_in"))
      (node (ref "SV") (pin "P$3") (pinfunction "P$3_P$3") (pintype "bidirectional"))
      (node (ref "SW1") (pin "LR") (pinfunction "LR_LR") (pintype "bidirectional"))
      (node (ref "U$1") (pin "VSS") (pinfunction "VSS_VSS") (pintype "power_in"))
      (node (ref "U$1") (pin "VSS2") (pinfunction "VSS2_VSS2") (pintype "power_in"))
      (node (ref "U$2") (pin "P2") (pinfunction "GND_P2") (pintype "bidirectional"))
      (node (ref "U$3") (pin "2") (pinfunction "VSS_2") (pintype "power_in"))
      (node (ref "U$3") (pin "8") (pinfunction "STBY_8") (pintype "input"))
      (node (ref "U$5") (pin "2") (pinfunction "VSS_2") (pintype "power_in"))
      (node (ref "U$5") (pin "8") (pinfunction "STBY_8") (pintype "input"))
      (node (ref "U$6") (pin "2") (pinfunction "VSS_2") (pintype "power_in"))
      (node (ref "U$6") (pin "8") (pinfunction "STBY_8") (pintype "input"))
    )
    (net (code "15") (name "GPSRX") (class "Default")
      (node (ref "STM1") (pin "PA2/UART2_TX") (pinfunction "PA2/UART2_TX_PA2/UART2_TX") (pintype "bidirectional"))
      (node (ref "U$2") (pin "P3") (pinfunction "RXD_P3") (pintype "bidirectional"))
    )
    (net (code "16") (name "GPSTX") (class "Default")
      (node (ref "STM1") (pin "PA3/UART2_RX") (pinfunction "PA3/UART2_RX_PA3/UART2_RX") (pintype "bidirectional"))
      (node (ref "U$2") (pin "P4") (pinfunction "TXD_P4") (pintype "bidirectional"))
    )
    (net (code "17") (name "IM_BUSY") (class "Default")
      (node (ref "IM1") (pin "$P1") (pinfunction "BUSY/IO1_$P1") (pintype "bidirectional"))
      (node (ref "STM1") (pin "PA5/SPI1_SCK") (pinfunction "PA5/SPI1_SCK_PA5/SPI1_SCK") (pintype "bidirectional"))
    )
    (net (code "18") (name "IM_RESET") (class "Default")
      (node (ref "IM1") (pin "$P19") (pinfunction "RESET_$P19") (pintype "bidirectional"))
      (node (ref "STM1") (pin "PA6/SPI1_MISO") (pinfunction "PA6/SPI1_MISO_PA6/SPI1_MISO") (pintype "bidirectional"))
    )
    (net (code "19") (name "IM_RX") (class "Default")
      (node (ref "IM1") (pin "$P6") (pinfunction "RXD/IO6_$P6") (pintype "bidirectional"))
      (node (ref "STM1") (pin "PA9/UART1_TX") (pinfunction "PA9/UART1_TX_PA9/UART1_TX") (pintype "bidirectional"))
    )
    (net (code "20") (name "IM_TX") (class "Default")
      (node (ref "IM1") (pin "$P7") (pinfunction "TXD/IO7_$P7") (pintype "bidirectional"))
      (node (ref "STM1") (pin "PA10/UART1_RX") (pinfunction "PA10/UART1_RX_PA10/UART1_RX") (pintype "bidirectional"))
    )
    (net (code "21") (name "LED") (class "Default")
      (node (ref "IM1") (pin "$P15") (pinfunction "STATUS_$P15") (pintype "bidirectional"))
      (node (ref "LED4") (pin "AN") (pinfunction "AN_AN") (pintype "bidirectional"))
    )
    (net (code "22") (name "LED0") (class "Default")
      (node (ref "LED0") (pin "AN") (pinfunction "AN_AN") (pintype "bidirectional"))
      (node (ref "STM0") (pin "PB0") (pinfunction "PB0_PB0") (pintype "bidirectional"))
    )
    (net (code "23") (name "LED1") (class "Default")
      (node (ref "LED1") (pin "AN") (pinfunction "AN_AN") (pintype "bidirectional"))
      (node (ref "STM0") (pin "PB1") (pinfunction "PB1_PB1") (pintype "bidirectional"))
    )
    (net (code "24") (name "LED1.0") (class "Default")
      (node (ref "LED2") (pin "AN") (pinfunction "AN_AN") (pintype "bidirectional"))
      (node (ref "STM1") (pin "PB0") (pinfunction "PB0_PB0") (pintype "bidirectional"))
    )
    (net (code "25") (name "LED1.1") (class "Default")
      (node (ref "LED3") (pin "AN") (pinfunction "AN_AN") (pintype "bidirectional"))
      (node (ref "STM1") (pin "PB1") (pinfunction "PB1_PB1") (pintype "bidirectional"))
    )
    (net (code "26") (name "LED2.0") (class "Default")
      (node (ref "LED5") (pin "AN") (pinfunction "AN_AN") (pintype "bidirectional"))
      (node (ref "U$1") (pin "PB0") (pinfunction "PB0_PB0") (pintype "bidirectional"))
    )
    (net (code "27") (name "LED2.1") (class "Default")
      (node (ref "LED6") (pin "AN") (pinfunction "AN_AN") (pintype "bidirectional"))
      (node (ref "U$1") (pin "PB1") (pinfunction "PB1_PB1") (pintype "bidirectional"))
    )
    (net (code "28") (name "LOGRX") (class "Default")
      (node (ref "STM0") (pin "PA9/UART1_TX") (pinfunction "PA9/UART1_TX_PA9/UART1_TX") (pintype "bidirectional"))
      (node (ref "U$1") (pin "PA10/UART1_RX") (pinfunction "PA10/UART1_RX_PA10/UART1_RX") (pintype "bidirectional"))
    )
    (net (code "29") (name "LOGTX") (class "Default")
      (node (ref "STM0") (pin "PA10/UART1_RX") (pinfunction "PA10/UART1_RX_PA10/UART1_RX") (pintype "bidirectional"))
      (node (ref "U$1") (pin "PA9/UART1_TX") (pinfunction "PA9/UART1_TX_PA9/UART1_TX") (pintype "bidirectional"))
    )
    (net (code "30") (name "MISO") (class "Default")
      (node (ref "CN1") (pin "DAT0") (pinfunction "DAT0_DAT0") (pintype "bidirectional"))
      (node (ref "R10") (pin "1") (pinfunction "1_1") (pintype "passive"))
      (node (ref "STM0") (pin "PA6/SPI1_MISO") (pinfunction "PA6/SPI1_MISO_PA6/SPI1_MISO") (pintype "bidirectional"))
    )
    (net (code "31") (name "MOSI") (class "Default")
      (node (ref "CN1") (pin "CMD") (pinfunction "CMD_CMD") (pintype "bidirectional"))
      (node (ref "R8") (pin "1") (pinfunction "1_1") (pintype "passive"))
      (node (ref "STM0") (pin "PA7/SPI1_MOSI") (pinfunction "PA7/SPI1_MOSI_PA7/SPI1_MOSI") (pintype "bidirectional"))
    )
    (net (code "32") (name "NRST0") (class "Default")
      (node (ref "C5") (pin "1") (pinfunction "1_1") (pintype "passive"))
      (node (ref "R2") (pin "1") (pinfunction "1_1") (pintype "passive"))
      (node (ref "RST") (pin "P$1") (pinfunction "P$1_P$1") (pintype "bidirectional"))
      (node (ref "STM0") (pin "NRST") (pinfunction "NRST_NRST") (pintype "bidirectional"))
    )
    (net (code "33") (name "NRST1") (class "Default")
      (node (ref "C14") (pin "1") (pinfunction "1_1") (pintype "passive"))
      (node (ref "R20") (pin "1") (pinfunction "1_1") (pintype "passive"))
      (node (ref "RST1") (pin "P$1") (pinfunction "P$1_P$1") (pintype "bidirectional"))
      (node (ref "STM1") (pin "NRST") (pinfunction "NRST_NRST") (pintype "bidirectional"))
    )
    (net (code "34") (name "NRST2") (class "Default")
      (node (ref "C19") (pin "1") (pinfunction "1_1") (pintype "passive"))
      (node (ref "R26") (pin "1") (pinfunction "1_1") (pintype "passive"))
      (node (ref "RST2") (pin "P$1") (pinfunction "P$1_P$1") (pintype "bidirectional"))
      (node (ref "U$1") (pin "NRST") (pinfunction "NRST_NRST") (pintype "bidirectional"))
    )
    (net (code "35") (name "NSS") (class "Default")
      (node (ref "CN1") (pin "CD/DAT3") (pinfunction "CD/DAT3_CD/DAT3") (pintype "bidirectional"))
      (node (ref "R7") (pin "1") (pinfunction "1_1") (pintype "passive"))
      (node (ref "STM0") (pin "PA4/SPI1_NSS") (pinfunction "PA4/SPI1_NSS_PA4/SPI1_NSS") (pintype "bidirectional"))
    )
    (net (code "36") (name "Net-(C20-Pad1)") (class "Default")
      (node (ref "C20") (pin "1") (pinfunction "1_1") (pintype "passive"))
      (node (ref "R36") (pin "1") (pinfunction "1_1") (pintype "passive"))
      (node (ref "R37") (pin "1") (pinfunction "1_1") (pintype "passive"))
    )
    (net (code "37") (name "Net-(C21-Pad1)") (class "Default")
      (node (ref "C21") (pin "1") (pinfunction "1_1") (pintype "passive"))
      (node (ref "R38") (pin "1") (pinfunction "1_1") (pintype "passive"))
      (node (ref "R39") (pin "1") (pinfunction "1_1") (pintype "passive"))
    )
    (net (code "38") (name "Net-(C22-Pad1)") (class "Default")
      (node (ref "C22") (pin "1") (pinfunction "1_1") (pintype "passive"))
      (node (ref "R40") (pin "1") (pinfunction "1_1") (pintype "passive"))
      (node (ref "R41") (pin "1") (pinfunction "1_1") (pintype "passive"))
    )
    (net (code "39") (name "Net-(CN1-PadCLK)") (class "Default")
      (node (ref "CN1") (pin "CLK") (pinfunction "CLK_CLK") (pintype "bidirectional"))
      (node (ref "R11") (pin "2") (pinfunction "2_2") (pintype "passive"))
      (node (ref "R9") (pin "1") (pinfunction "1_1") (pintype "passive"))
    )
    (net (code "40") (name "Net-(D1-PadC)") (class "Default")
      (node (ref "D1") (pin "C") (pinfunction "C_C") (pintype "passive"))
      (node (ref "MOS1") (pin "4") (pinfunction "4_4") (pintype "bidirectional"))
      (node (ref "MOS3") (pin "4") (pinfunction "4_4") (pintype "bidirectional"))
      (node (ref "R16") (pin "2") (pinfunction "2_2") (pintype "passive"))
    )
    (net (code "41") (name "Net-(D2-PadC)") (class "Default")
      (node (ref "D2") (pin "C") (pinfunction "C_C") (pintype "passive"))
      (node (ref "MOS2") (pin "4") (pinfunction "4_4") (pintype "bidirectional"))
      (node (ref "MOS6") (pin "4") (pinfunction "4_4") (pintype "bidirectional"))
      (node (ref "R15") (pin "2") (pinfunction "2_2") (pintype "passive"))
    )
    (net (code "42") (name "Net-(D3-PadC)") (class "Default")
      (node (ref "D3") (pin "C") (pinfunction "C_C") (pintype "passive"))
      (node (ref "MOS10") (pin "4") (pinfunction "4_4") (pintype "bidirectional"))
      (node (ref "MOS9") (pin "4") (pinfunction "4_4") (pintype "bidirectional"))
      (node (ref "R18") (pin "2") (pinfunction "2_2") (pintype "passive"))
    )
    (net (code "43") (name "Net-(DCDC1-PadVIN)") (class "Default")
      (node (ref "DCDC1") (pin "VIN") (pinfunction "VIN_VIN") (pintype "bidirectional"))
      (node (ref "MOS1") (pin "1") (pinfunction "1_1") (pintype "bidirectional"))
      (node (ref "MOS1") (pin "2") (pinfunction "2_2") (pintype "bidirectional"))
      (node (ref "MOS1") (pin "5") (pinfunction "5_5") (pintype "bidirectional"))
      (node (ref "MOS1") (pin "6") (pinfunction "6_6") (pintype "bidirectional"))
    )
    (net (code "44") (name "Net-(DCDC2-PadVIN)") (class "Default")
      (node (ref "DCDC2") (pin "VIN") (pinfunction "VIN_VIN") (pintype "bidirectional"))
      (node (ref "MOS2") (pin "1") (pinfunction "1_1") (pintype "bidirectional"))
      (node (ref "MOS2") (pin "2") (pinfunction "2_2") (pintype "bidirectional"))
      (node (ref "MOS2") (pin "5") (pinfunction "5_5") (pintype "bidirectional"))
      (node (ref "MOS2") (pin "6") (pinfunction "6_6") (pintype "bidirectional"))
    )
    (net (code "45") (name "Net-(DCDC3-PadVIN)") (class "Default")
      (node (ref "DCDC3") (pin "VIN") (pinfunction "VIN_VIN") (pintype "bidirectional"))
      (node (ref "MOS10") (pin "1") (pinfunction "1_1") (pintype "bidirectional"))
      (node (ref "MOS10") (pin "2") (pinfunction "2_2") (pintype "bidirectional"))
      (node (ref "MOS10") (pin "5") (pinfunction "5_5") (pintype "bidirectional"))
      (node (ref "MOS10") (pin "6") (pinfunction "6_6") (pintype "bidirectional"))
    )
    (net (code "46") (name "Net-(LED0-PadCT)") (class "Default")
      (node (ref "LED0") (pin "CT") (pinfunction "CT_CT") (pintype "bidirectional"))
      (node (ref "R5") (pin "2") (pinfunction "2_2") (pintype "passive"))
    )
    (net (code "47") (name "Net-(LED1-PadCT)") (class "Default")
      (node (ref "LED1") (pin "CT") (pinfunction "CT_CT") (pintype "bidirectional"))
      (node (ref "R6") (pin "2") (pinfunction "2_2") (pintype "passive"))
    )
    (net (code "48") (name "Net-(LED2-PadCT)") (class "Default")
      (node (ref "LED2") (pin "CT") (pinfunction "CT_CT") (pintype "bidirectional"))
      (node (ref "R22") (pin "2") (pinfunction "2_2") (pintype "passive"))
    )
    (net (code "49") (name "Net-(LED3-PadCT)") (class "Default")
      (node (ref "LED3") (pin "CT") (pinfunction "CT_CT") (pintype "bidirectional"))
      (node (ref "R23") (pin "2") (pinfunction "2_2") (pintype "passive"))
    )
    (net (code "50") (name "Net-(LED4-PadCT)") (class "Default")
      (node (ref "LED4") (pin "CT") (pinfunction "CT_CT") (pintype "bidirectional"))
      (node (ref "R24") (pin "2") (pinfunction "2_2") (pintype "passive"))
    )
    (net (code "51") (name "Net-(LED5-PadCT)") (class "Default")
      (node (ref "LED5") (pin "CT") (pinfunction "CT_CT") (pintype "bidirectional"))
      (node (ref "R28") (pin "2") (pinfunction "2_2") (pintype "passive"))
    )
    (net (code "52") (name "Net-(LED6-PadCT)") (class "Default")
      (node (ref "LED6") (pin "CT") (pinfunction "CT_CT") (pintype "bidirectional"))
      (node (ref "R29") (pin "2") (pinfunction "2_2") (pintype "passive"))
    )
    (net (code "53") (name "Net-(MOS3-Pad1)") (class "Default")
      (node (ref "MOS3") (pin "1") (pinfunction "1_1") (pintype "bidirectional"))
      (node (ref "MOS3") (pin "2") (pinfunction "2_2") (pintype "bidirectional"))
      (node (ref "MOS3") (pin "5") (pinfunction "5_5") (pintype "bidirectional"))
      (node (ref "MOS3") (pin "6") (pinfunction "6_6") (pintype "bidirectional"))
      (node (ref "MOS7") (pin "1") (pinfunction "1_1") (pintype "bidirectional"))
      (node (ref "MOS7") (pin "2") (pinfunction "2_2") (pintype "bidirectional"))
      (node (ref "MOS7") (pin "5") (pinfunction "5_5") (pintype "bidirectional"))
      (node (ref "MOS7") (pin "6") (pinfunction "6_6") (pintype "bidirectional"))
    )
    (net (code "54") (name "Net-(MOS4-Pad1)") (class "Default")
      (node (ref "MOS4") (pin "1") (pinfunction "1_1") (pintype "bidirectional"))
      (node (ref "MOS4") (pin "2") (pinfunction "2_2") (pintype "bidirectional"))
      (node (ref "MOS4") (pin "5") (pinfunction "5_5") (pintype "bidirectional"))
      (node (ref "MOS4") (pin "6") (pinfunction "6_6") (pintype "bidirectional"))
      (node (ref "MOS6") (pin "1") (pinfunction "1_1") (pintype "bidirectional"))
      (node (ref "MOS6") (pin "2") (pinfunction "2_2") (pintype "bidirectional"))
      (node (ref "MOS6") (pin "5") (pinfunction "5_5") (pintype "bidirectional"))
      (node (ref "MOS6") (pin "6") (pinfunction "6_6") (pintype "bidirectional"))
    )
    (net (code "55") (name "Net-(MOS5-Pad1)") (class "Default")
      (node (ref "MOS5") (pin "1") (pinfunction "1_1") (pintype "bidirectional"))
      (node (ref "MOS5") (pin "2") (pinfunction "2_2") (pintype "bidirectional"))
      (node (ref "MOS5") (pin "5") (pinfunction "5_5") (pintype "bidirectional"))
      (node (ref "MOS5") (pin "6") (pinfunction "6_6") (pintype "bidirectional"))
      (node (ref "R13") (pin "1") (pinfunction "1_1") (pintype "passive"))
      (node (ref "R14") (pin "2") (pinfunction "2_2") (pintype "passive"))
    )
    (net (code "56") (name "Net-(MOS8-Pad1)") (class "Default")
      (node (ref "MOS8") (pin "1") (pinfunction "1_1") (pintype "bidirectional"))
      (node (ref "MOS8") (pin "2") (pinfunction "2_2") (pintype "bidirectional"))
      (node (ref "MOS8") (pin "5") (pinfunction "5_5") (pintype "bidirectional"))
      (node (ref "MOS8") (pin "6") (pinfunction "6_6") (pintype "bidirectional"))
      (node (ref "MOS9") (pin "1") (pinfunction "1_1") (pintype "bidirectional"))
      (node (ref "MOS9") (pin "2") (pinfunction "2_2") (pintype "bidirectional"))
      (node (ref "MOS9") (pin "5") (pinfunction "5_5") (pintype "bidirectional"))
      (node (ref "MOS9") (pin "6") (pinfunction "6_6") (pintype "bidirectional"))
    )
    (net (code "57") (name "Net-(PWR-PadCT)") (class "Default")
      (node (ref "PWR") (pin "CT") (pinfunction "CT_CT") (pintype "bidirectional"))
      (node (ref "R3") (pin "2") (pinfunction "2_2") (pintype "passive"))
    )
    (net (code "58") (name "Net-(PWR1-PadCT)") (class "Default")
      (node (ref "PWR1") (pin "CT") (pinfunction "CT_CT") (pintype "bidirectional"))
      (node (ref "R21") (pin "2") (pinfunction "2_2") (pintype "passive"))
    )
    (net (code "59") (name "Net-(PWR2-PadCT)") (class "Default")
      (node (ref "PWR2") (pin "CT") (pinfunction "CT_CT") (pintype "bidirectional"))
      (node (ref "R27") (pin "2") (pinfunction "2_2") (pintype "passive"))
    )
    (net (code "60") (name "OSC_IN1") (class "Default")
      (node (ref "STM1") (pin "PF0") (pinfunction "PF0_PF0") (pintype "bidirectional"))
    )
    (net (code "61") (name "OSC_IN2") (class "Default")
      (node (ref "U$1") (pin "PF0") (pinfunction "PF0_PF0") (pintype "bidirectional"))
    )
    (net (code "62") (name "OSC_OUT1") (class "Default")
      (node (ref "STM1") (pin "PF1") (pinfunction "PF1_PF1") (pintype "bidirectional"))
    )
    (net (code "63") (name "OSC_OUT2") (class "Default")
      (node (ref "U$1") (pin "PF1") (pinfunction "PF1_PF1") (pintype "bidirectional"))
    )
    (net (code "64") (name "PWM") (class "Default")
      (node (ref "SV") (pin "P$1") (pinfunction "P$1_P$1") (pintype "bidirectional"))
      (node (ref "U$1") (pin "PA5/SPI1_SCK") (pinfunction "PA5/SPI1_SCK_PA5/SPI1_SCK") (pintype "bidirectional"))
    )
    (net (code "65") (name "RXCAN") (class "Default")
      (node (ref "STM0") (pin "PA12/CAN_TX") (pinfunction "PA12/CAN_TX_PA12/CAN_TX") (pintype "bidirectional"))
      (node (ref "U$3") (pin "4") (pinfunction "RXD_4") (pintype "output"))
    )
    (net (code "66") (name "RXCAN1") (class "Default")
      (node (ref "STM1") (pin "PA12/CAN_TX") (pinfunction "PA12/CAN_TX_PA12/CAN_TX") (pintype "bidirectional"))
      (node (ref "U$5") (pin "4") (pinfunction "RXD_4") (pintype "output"))
    )
    (net (code "67") (name "RXCAN2") (class "Default")
      (node (ref "U$1") (pin "PA12/CAN_TX") (pinfunction "PA12/CAN_TX_PA12/CAN_TX") (pintype "bidirectional"))
      (node (ref "U$6") (pin "4") (pinfunction "RXD_4") (pintype "output"))
    )
    (net (code "68") (name "SCK") (class "Default")
      (node (ref "R11") (pin "1") (pinfunction "1_1") (pintype "passive"))
      (node (ref "STM0") (pin "PA5/SPI1_SCK") (pinfunction "PA5/SPI1_SCK_PA5/SPI1_SCK") (pintype "bidirectional"))
    )
    (net (code "69") (name "SCL0") (class "Default")
      (node (ref "BMP1") (pin "P3") (pinfunction "SCL_P3") (pintype "bidirectional"))
      (node (ref "BMX1") (pin "SCL") (pinfunction "SCL_SCL") (pintype "bidirectional"))
      (node (ref "R33") (pin "2") (pinfunction "2_2") (pintype "passive"))
      (node (ref "STM0") (pin "PA15/I2C1_SCL") (pinfunction "PA15/I2C1_SCL_PA15/I2C1_SCL") (pintype "bidirectional"))
    )
    (net (code "70") (name "SCL1") (class "Default")
      (node (ref "BMP3") (pin "P3") (pinfunction "SCL_P3") (pintype "bidirectional"))
      (node (ref "R35") (pin "2") (pinfunction "2_2") (pintype "passive"))
      (node (ref "STM1") (pin "PA15/I2C1_SCL") (pinfunction "PA15/I2C1_SCL_PA15/I2C1_SCL") (pintype "bidirectional"))
    )
    (net (code "71") (name "SCL2") (class "Default")
      (node (ref "BMP2") (pin "P3") (pinfunction "SCL_P3") (pintype "bidirectional"))
      (node (ref "BMX2") (pin "SCL") (pinfunction "SCL_SCL") (pintype "bidirectional"))
      (node (ref "R31") (pin "2") (pinfunction "2_2") (pintype "passive"))
      (node (ref "U$1") (pin "PA15/I2C1_SCL") (pinfunction "PA15/I2C1_SCL_PA15/I2C1_SCL") (pintype "bidirectional"))
    )
    (net (code "72") (name "SDA0") (class "Default")
      (node (ref "BMP1") (pin "P4") (pinfunction "SDA_P4") (pintype "bidirectional"))
      (node (ref "BMX1") (pin "SDA") (pinfunction "SDA_SDA") (pintype "bidirectional"))
      (node (ref "R32") (pin "1") (pinfunction "1_1") (pintype "passive"))
      (node (ref "STM0") (pin "PB7/I2C1_SDA") (pinfunction "PB7/I2C1_SDA_PB7/I2C1_SDA") (pintype "bidirectional"))
    )
    (net (code "73") (name "SDA1") (class "Default")
      (node (ref "BMP3") (pin "P4") (pinfunction "SDA_P4") (pintype "bidirectional"))
      (node (ref "R34") (pin "1") (pinfunction "1_1") (pintype "passive"))
      (node (ref "STM1") (pin "PB7/I2C1_SDA") (pinfunction "PB7/I2C1_SDA_PB7/I2C1_SDA") (pintype "bidirectional"))
    )
    (net (code "74") (name "SDA2") (class "Default")
      (node (ref "BMP2") (pin "P4") (pinfunction "SDA_P4") (pintype "bidirectional"))
      (node (ref "BMX2") (pin "SDA") (pinfunction "SDA_SDA") (pintype "bidirectional"))
      (node (ref "R30") (pin "1") (pinfunction "1_1") (pintype "passive"))
      (node (ref "U$1") (pin "PB7/I2C1_SDA") (pinfunction "PB7/I2C1_SDA_PB7/I2C1_SDA") (pintype "bidirectional"))
    )
    (net (code "75") (name "SW") (class "Default")
      (node (ref "MOS1") (pin "3") (pinfunction "3_3") (pintype "bidirectional"))
      (node (ref "MOS10") (pin "3") (pinfunction "3_3") (pintype "bidirectional"))
      (node (ref "MOS2") (pin "3") (pinfunction "3_3") (pintype "bidirectional"))
      (node (ref "R15") (pin "1") (pinfunction "1_1") (pintype "passive"))
      (node (ref "R16") (pin "1") (pinfunction "1_1") (pintype "passive"))
      (node (ref "R18") (pin "1") (pinfunction "1_1") (pintype "passive"))
      (node (ref "SW1") (pin "L") (pinfunction "L_L") (pintype "bidirectional"))
    )
    (net (code "76") (name "SWCLK") (class "Default")
      (node (ref "JP1") (pin "3") (pinfunction "3_3") (pintype "passive"))
      (node (ref "STM0") (pin "PA14/SWCLK") (pinfunction "PA14/SWCLK_PA14/SWCLK") (pintype "bidirectional"))
    )
    (net (code "77") (name "SWCLK1") (class "Default")
      (node (ref "JP3") (pin "3") (pinfunction "3_3") (pintype "passive"))
      (node (ref "STM1") (pin "PA14/SWCLK") (pinfunction "PA14/SWCLK_PA14/SWCLK") (pintype "bidirectional"))
    )
    (net (code "78") (name "SWCLK2") (class "Default")
      (node (ref "JP4") (pin "3") (pinfunction "3_3") (pintype "passive"))
      (node (ref "U$1") (pin "PA14/SWCLK") (pinfunction "PA14/SWCLK_PA14/SWCLK") (pintype "bidirectional"))
    )
    (net (code "79") (name "SWDIO") (class "Default")
      (node (ref "JP1") (pin "1") (pinfunction "1_1") (pintype "passive"))
      (node (ref "STM0") (pin "PA13/SWDIO") (pinfunction "PA13/SWDIO_PA13/SWDIO") (pintype "bidirectional"))
    )
    (net (code "80") (name "SWDIO1") (class "Default")
      (node (ref "JP3") (pin "1") (pinfunction "1_1") (pintype "passive"))
      (node (ref "STM1") (pin "PA13/SWDIO") (pinfunction "PA13/SWDIO_PA13/SWDIO") (pintype "bidirectional"))
    )
    (net (code "81") (name "SWDIO2") (class "Default")
      (node (ref "JP4") (pin "5") (pinfunction "5_5") (pintype "passive"))
      (node (ref "U$1") (pin "PA13/SWDIO") (pinfunction "PA13/SWDIO_PA13/SWDIO") (pintype "bidirectional"))
    )
    (net (code "82") (name "SWO") (class "Default")
      (node (ref "JP1") (pin "5") (pinfunction "5_5") (pintype "passive"))
      (node (ref "STM0") (pin "PB3/SWO") (pinfunction "PB3/TRACESWO_PB3/SWO") (pintype "bidirectional"))
    )
    (net (code "83") (name "SWO1") (class "Default")
      (node (ref "JP3") (pin "5") (pinfunction "5_5") (pintype "passive"))
      (node (ref "STM1") (pin "PB3/SWO") (pinfunction "PB3/TRACESWO_PB3/SWO") (pintype "bidirectional"))
    )
    (net (code "84") (name "SWO2") (class "Default")
      (node (ref "JP4") (pin "1") (pinfunction "1_1") (pintype "passive"))
      (node (ref "U$1") (pin "PB3/SWO") (pinfunction "PB3/TRACESWO_PB3/SWO") (pintype "bidirectional"))
    )
    (net (code "85") (name "TXCAN") (class "Default")
      (node (ref "STM0") (pin "PA11/CAN_RX") (pinfunction "PA11/CAN_RX_PA11/CAN_RX") (pintype "bidirectional"))
      (node (ref "U$3") (pin "1") (pinfunction "TXD_1") (pintype "input"))
    )
    (net (code "86") (name "TXCAN1") (class "Default")
      (node (ref "STM1") (pin "PA11/CAN_RX") (pinfunction "PA11/CAN_RX_PA11/CAN_RX") (pintype "bidirectional"))
      (node (ref "U$5") (pin "1") (pinfunction "TXD_1") (pintype "input"))
    )
    (net (code "87") (name "TXCAN2") (class "Default")
      (node (ref "U$1") (pin "PA11/CAN_RX") (pinfunction "PA11/CAN_RX_PA11/CAN_RX") (pintype "bidirectional"))
      (node (ref "U$6") (pin "1") (pinfunction "TXD_1") (pintype "input"))
    )
    (net (code "88") (name "unconnected-(CN1-PadDAT1)") (class "Default")
      (node (ref "CN1") (pin "DAT1") (pinfunction "DAT1_DAT1") (pintype "bidirectional"))
    )
    (net (code "89") (name "unconnected-(CN1-PadDAT2)") (class "Default")
      (node (ref "CN1") (pin "DAT2") (pinfunction "DAT2_DAT2") (pintype "bidirectional"))
    )
    (net (code "90") (name "unconnected-(CN1-PadDET_A)") (class "Default")
      (node (ref "CN1") (pin "DET_A") (pinfunction "DET_A_DET_A") (pintype "bidirectional"))
    )
    (net (code "91") (name "unconnected-(CN1-PadDET_B)") (class "Default")
      (node (ref "CN1") (pin "DET_B") (pinfunction "DET_B_DET_B") (pintype "bidirectional"))
    )
    (net (code "92") (name "unconnected-(IM1-IO2-Pad$P2)") (class "Default")
      (node (ref "IM1") (pin "$P2") (pinfunction "IO2_$P2") (pintype "bidirectional"))
    )
    (net (code "93") (name "unconnected-(IM1-IO5-Pad$P5)") (class "Default")
      (node (ref "IM1") (pin "$P5") (pinfunction "IO5_$P5") (pintype "bidirectional"))
    )
    (net (code "94") (name "unconnected-(IM1-IO8-Pad$P8)") (class "Default")
      (node (ref "IM1") (pin "$P8") (pinfunction "IO8_$P8") (pintype "bidirectional"))
    )
    (net (code "95") (name "unconnected-(IM1-MODE1{slash}IO9-Pad$P9)") (class "Default")
      (node (ref "IM1") (pin "$P9") (pinfunction "MODE1/IO9_$P9") (pintype "bidirectional"))
    )
    (net (code "96") (name "unconnected-(IM1-MODE2{slash}IO10-Pad$P10)") (class "Default")
      (node (ref "IM1") (pin "$P10") (pinfunction "MODE2/IO10_$P10") (pintype "bidirectional"))
    )
    (net (code "97") (name "unconnected-(IM1-REG-Pad$P16)") (class "Default")
      (node (ref "IM1") (pin "$P16") (pinfunction "REG_$P16") (pintype "bidirectional"))
    )
    (net (code "98") (name "unconnected-(IM1-SLEEP{slash}IO4-Pad$P4)") (class "Default")
      (node (ref "IM1") (pin "$P4") (pinfunction "SLEEP/IO4_$P4") (pintype "bidirectional"))
    )
    (net (code "99") (name "unconnected-(IM1-XMIT{slash}IO3-Pad$P3)") (class "Default")
      (node (ref "IM1") (pin "$P3") (pinfunction "XMIT/IO3_$P3") (pintype "bidirectional"))
    )
    (net (code "100") (name "unconnected-(JP1-Pad4)") (class "Default")
      (node (ref "JP1") (pin "4") (pinfunction "4_4") (pintype "passive"))
    )
    (net (code "101") (name "unconnected-(JP3-Pad4)") (class "Default")
      (node (ref "JP3") (pin "4") (pinfunction "4_4") (pintype "passive"))
    )
    (net (code "102") (name "unconnected-(JP4-Pad4)") (class "Default")
      (node (ref "JP4") (pin "4") (pinfunction "4_4") (pintype "passive"))
    )
    (net (code "103") (name "unconnected-(STM0-PadPA0)") (class "Default")
      (node (ref "STM0") (pin "PA0") (pinfunction "PA0_PA0") (pintype "bidirectional"))
    )
    (net (code "104") (name "unconnected-(STM0-PadPA1)") (class "Default")
      (node (ref "STM0") (pin "PA1") (pinfunction "PA1_PA1") (pintype "bidirectional"))
    )
    (net (code "105") (name "unconnected-(STM0-PadPA2{slash}UART2_TX)") (class "Default")
      (node (ref "STM0") (pin "PA2/UART2_TX") (pinfunction "PA2/UART2_TX_PA2/UART2_TX") (pintype "bidirectional"))
    )
    (net (code "106") (name "unconnected-(STM0-PadPA3{slash}UART2_RX)") (class "Default")
      (node (ref "STM0") (pin "PA3/UART2_RX") (pinfunction "PA3/UART2_RX_PA3/UART2_RX") (pintype "bidirectional"))
    )
    (net (code "107") (name "unconnected-(STM0-PadPA8)") (class "Default")
      (node (ref "STM0") (pin "PA8") (pinfunction "PA8_PA8") (pintype "bidirectional"))
    )
    (net (code "108") (name "unconnected-(STM0-PadPB5)") (class "Default")
      (node (ref "STM0") (pin "PB5") (pinfunction "PB5_PB5") (pintype "bidirectional"))
    )
    (net (code "109") (name "unconnected-(STM0-PadPB6)") (class "Default")
      (node (ref "STM0") (pin "PB6") (pinfunction "PB6_PB6") (pintype "bidirectional"))
    )
    (net (code "110") (name "unconnected-(STM0-PadPF0)") (class "Default")
      (node (ref "STM0") (pin "PF0") (pinfunction "PF0_PF0") (pintype "bidirectional"))
    )
    (net (code "111") (name "unconnected-(STM0-PadPF1)") (class "Default")
      (node (ref "STM0") (pin "PF1") (pinfunction "PF1_PF1") (pintype "bidirectional"))
    )
    (net (code "112") (name "unconnected-(STM1-PadPA0)") (class "Default")
      (node (ref "STM1") (pin "PA0") (pinfunction "PA0_PA0") (pintype "bidirectional"))
    )
    (net (code "113") (name "unconnected-(STM1-PadPA1)") (class "Default")
      (node (ref "STM1") (pin "PA1") (pinfunction "PA1_PA1") (pintype "bidirectional"))
    )
    (net (code "114") (name "unconnected-(STM1-PadPA4{slash}SPI1_NSS)") (class "Default")
      (node (ref "STM1") (pin "PA4/SPI1_NSS") (pinfunction "PA4/SPI1_NSS_PA4/SPI1_NSS") (pintype "bidirectional"))
    )
    (net (code "115") (name "unconnected-(STM1-PadPA7{slash}SPI1_MOSI)") (class "Default")
      (node (ref "STM1") (pin "PA7/SPI1_MOSI") (pinfunction "PA7/SPI1_MOSI_PA7/SPI1_MOSI") (pintype "bidirectional"))
    )
    (net (code "116") (name "unconnected-(STM1-PadPA8)") (class "Default")
      (node (ref "STM1") (pin "PA8") (pinfunction "PA8_PA8") (pintype "bidirectional"))
    )
    (net (code "117") (name "unconnected-(STM1-PadPB5)") (class "Default")
      (node (ref "STM1") (pin "PB5") (pinfunction "PB5_PB5") (pintype "bidirectional"))
    )
    (net (code "118") (name "unconnected-(STM1-PadPB6)") (class "Default")
      (node (ref "STM1") (pin "PB6") (pinfunction "PB6_PB6") (pintype "bidirectional"))
    )
    (net (code "119") (name "unconnected-(SW1-PadR)") (class "Default")
      (node (ref "SW1") (pin "R") (pinfunction "R_R") (pintype "bidirectional"))
    )
    (net (code "120") (name "unconnected-(U$1-PadPA0)") (class "Default")
      (node (ref "U$1") (pin "PA0") (pinfunction "PA0_PA0") (pintype "bidirectional"))
    )
    (net (code "121") (name "unconnected-(U$1-PadPA1)") (class "Default")
      (node (ref "U$1") (pin "PA1") (pinfunction "PA1_PA1") (pintype "bidirectional"))
    )
    (net (code "122") (name "unconnected-(U$1-PadPA2{slash}UART2_TX)") (class "Default")
      (node (ref "U$1") (pin "PA2/UART2_TX") (pinfunction "PA2/UART2_TX_PA2/UART2_TX") (pintype "bidirectional"))
    )
    (net (code "123") (name "unconnected-(U$1-PadPA3{slash}UART2_RX)") (class "Default")
      (node (ref "U$1") (pin "PA3/UART2_RX") (pinfunction "PA3/UART2_RX_PA3/UART2_RX") (pintype "bidirectional"))
    )
    (net (code "124") (name "unconnected-(U$1-PadPA4{slash}SPI1_NSS)") (class "Default")
      (node (ref "U$1") (pin "PA4/SPI1_NSS") (pinfunction "PA4/SPI1_NSS_PA4/SPI1_NSS") (pintype "bidirectional"))
    )
    (net (code "125") (name "unconnected-(U$1-PadPA6{slash}SPI1_MISO)") (class "Default")
      (node (ref "U$1") (pin "PA6/SPI1_MISO") (pinfunction "PA6/SPI1_MISO_PA6/SPI1_MISO") (pintype "bidirectional"))
    )
    (net (code "126") (name "unconnected-(U$1-PadPA7{slash}SPI1_MOSI)") (class "Default")
      (node (ref "U$1") (pin "PA7/SPI1_MOSI") (pinfunction "PA7/SPI1_MOSI_PA7/SPI1_MOSI") (pintype "bidirectional"))
    )
    (net (code "127") (name "unconnected-(U$1-PadPA8)") (class "Default")
      (node (ref "U$1") (pin "PA8") (pinfunction "PA8_PA8") (pintype "bidirectional"))
    )
    (net (code "128") (name "unconnected-(U$1-PadPB5)") (class "Default")
      (node (ref "U$1") (pin "PB5") (pinfunction "PB5_PB5") (pintype "bidirectional"))
    )
    (net (code "129") (name "unconnected-(U$1-PadPB6)") (class "Default")
      (node (ref "U$1") (pin "PB6") (pinfunction "PB6_PB6") (pintype "bidirectional"))
    )
    (net (code "130") (name "unconnected-(U$2-1PPS-PadP5)") (class "Default")
      (node (ref "U$2") (pin "P5") (pinfunction "1PPS_P5") (pintype "bidirectional"))
    )
  )
)
